# Schematic.net
KiCad netlist of a schematic drawn in Altium Designer
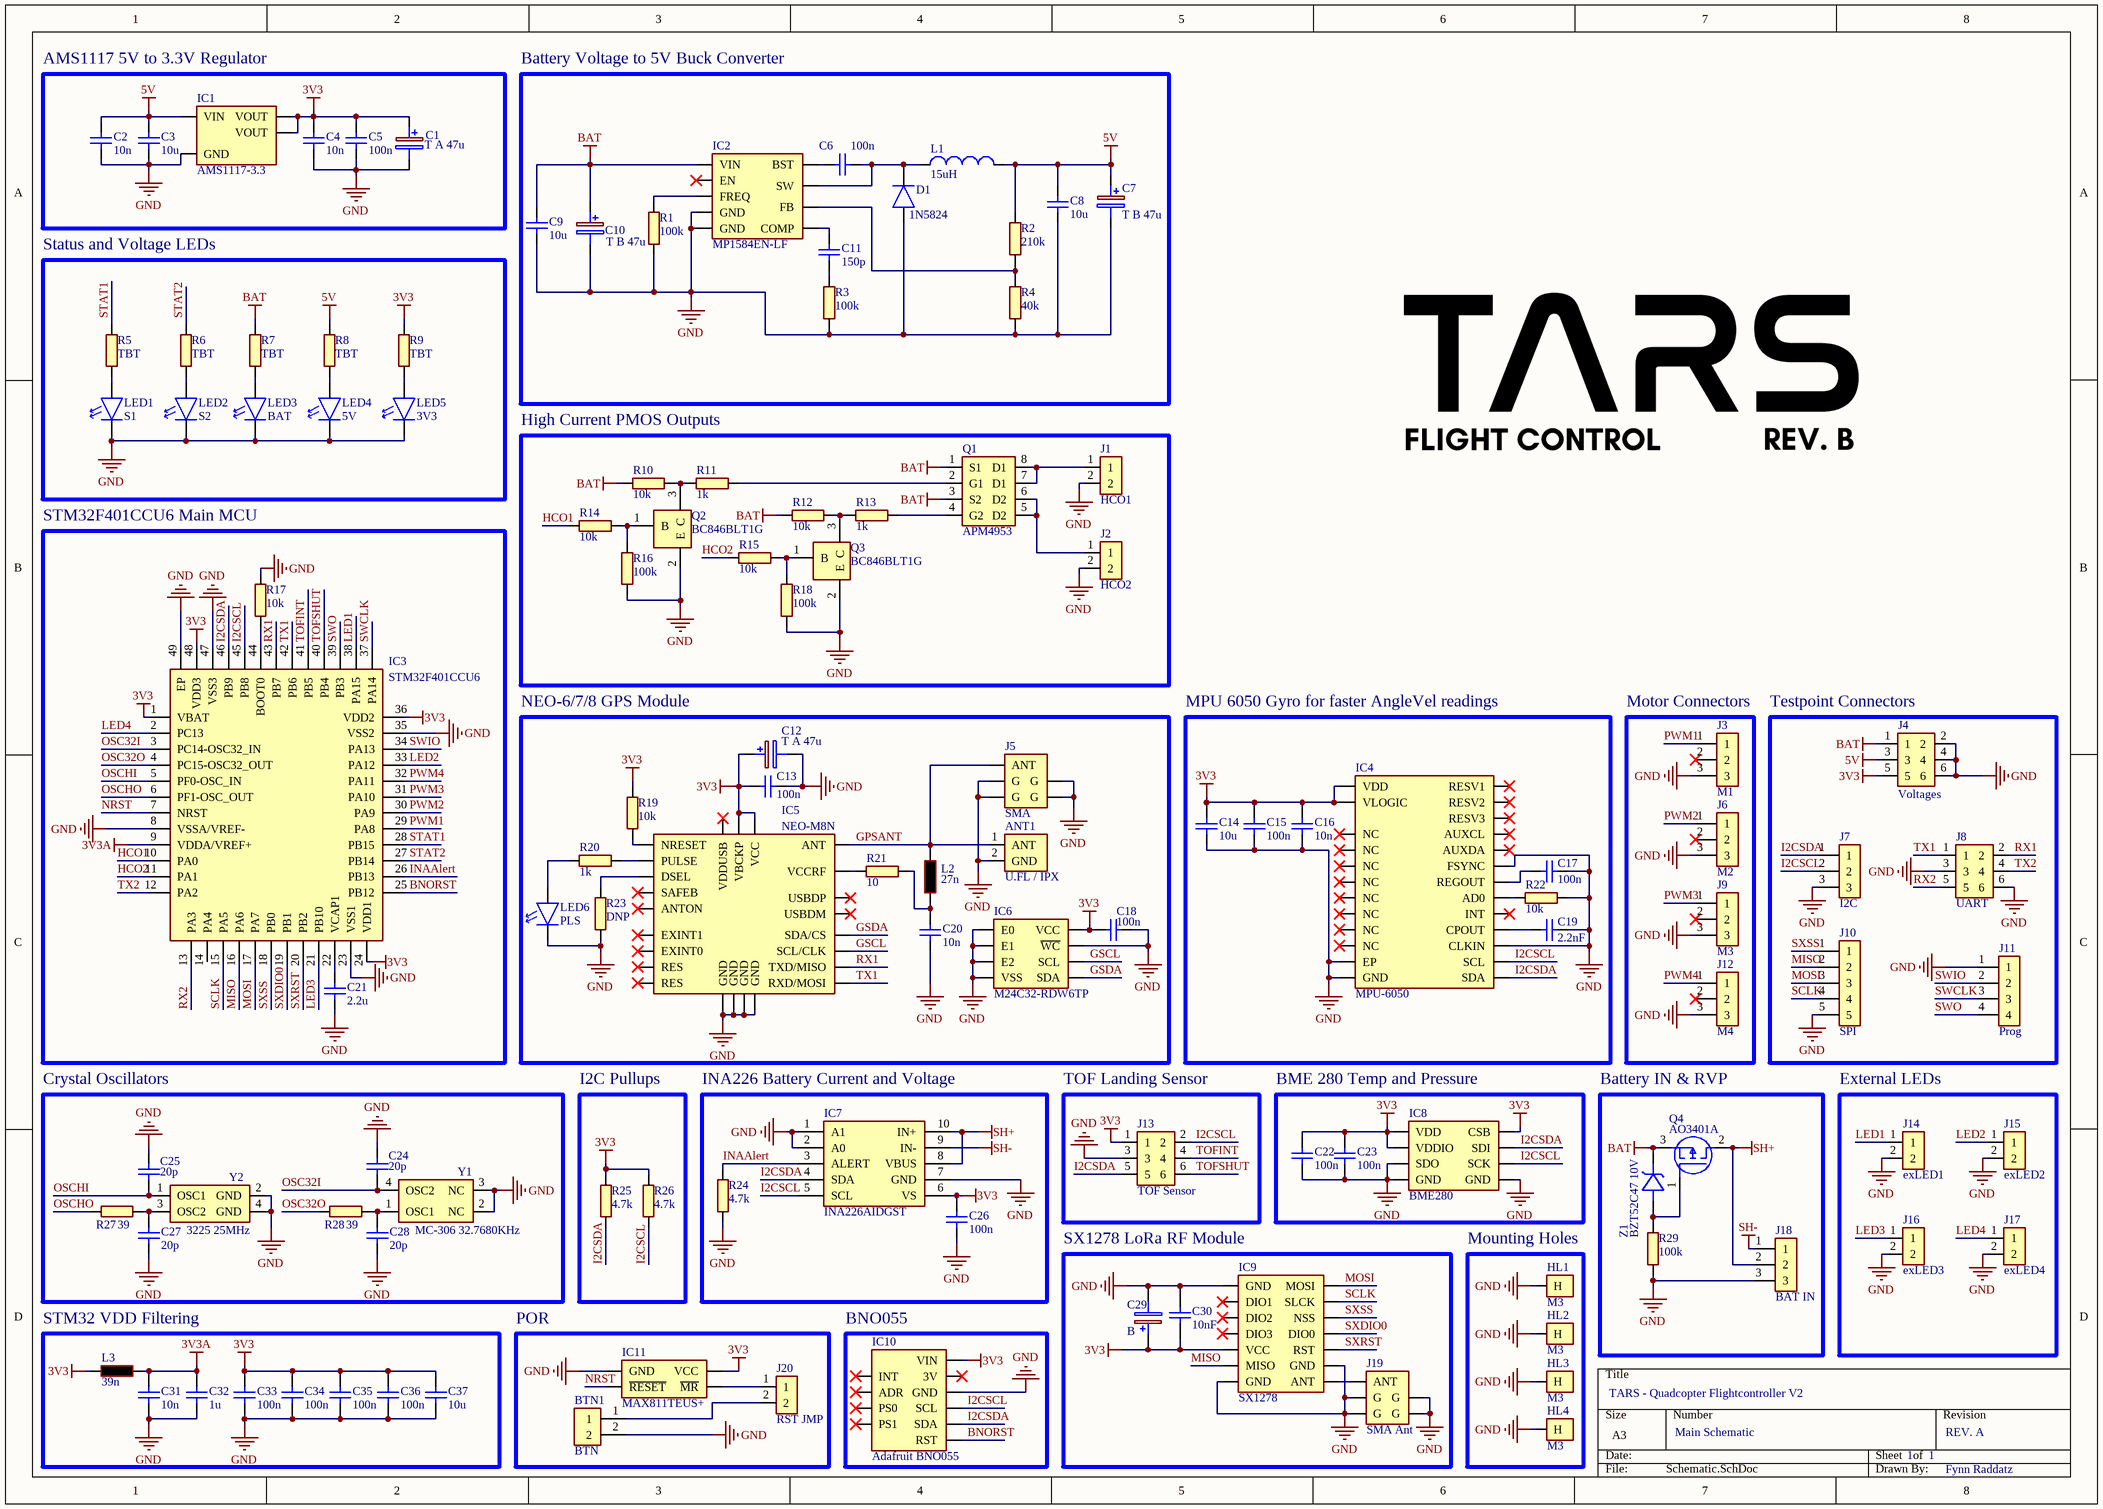
[diagram p0: Schematic.SchDoc]

(export (version "E")
  (design (tool "Eeschema 10.0.6"))
  (components
    (comp (ref "ANT1")
      (value "U.FL / IPX")
      (footprint "U.FL IPX Connector")
      (description "Connector")
      (libsource (lib "SamacSys") (part "U.FL SMD Antenna Connector"))
    )
    (comp (ref "BTN1")
      (value "BTN")
      (footprint "SamacSys:SMD-Button-3*6mm")
      (description "Button")
      (libsource (lib "SamacSys") (part "SMDButton-3*6mm"))
    )
    (comp (ref "C1")
      (value "T A 47u")
      (footprint "Tantal-A-1206")
      (description "Capacitor Tantalum")
      (libsource (lib "SamacSys") (part "TANTAL-A"))
    )
    (comp (ref "C2")
      (value "10n")
      (footprint "CAPC2012 METRIC")
      (description "Capacitor")
      (fields (field (name "MANUFACTURER_PART_NUMBER") "CL21B104KACNNNC"))
      (libsource (lib "SamacSys") (part "Cap 0805 IMP"))
    )
    (comp (ref "C3")
      (value "10u")
      (footprint "CAPC2012 METRIC")
      (description "Capacitor")
      (fields (field (name "MANUFACTURER_PART_NUMBER") "CL21B104KACNNNC"))
      (libsource (lib "SamacSys") (part "Cap 0805 IMP"))
    )
    (comp (ref "C4")
      (value "10n")
      (footprint "CAPC2012 METRIC")
      (description "Capacitor")
      (fields (field (name "MANUFACTURER_PART_NUMBER") "CL21B104KACNNNC"))
      (libsource (lib "SamacSys") (part "Cap 0805 IMP"))
    )
    (comp (ref "C5")
      (value "100n")
      (footprint "CAPC2012 METRIC")
      (description "Capacitor")
      (fields (field (name "MANUFACTURER_PART_NUMBER") "CL21B104KACNNNC"))
      (libsource (lib "SamacSys") (part "Cap 0805 IMP"))
    )
    (comp (ref "C6")
      (value "100n")
      (footprint "CAPC2012 METRIC")
      (description "Capacitor")
      (fields (field (name "MANUFACTURER_PART_NUMBER") "CL21B104KACNNNC"))
      (libsource (lib "SamacSys") (part "Cap 0805 IMP"))
    )
    (comp (ref "C7")
      (value "T B 47u")
      (footprint "Tantal-B-1210")
      (description "Capacitor Tantalum")
      (libsource (lib "SamacSys") (part "TANTAL-B"))
    )
    (comp (ref "C8")
      (value "10u")
      (footprint "CAPC2012 METRIC")
      (description "Capacitor")
      (fields (field (name "MANUFACTURER_PART_NUMBER") "CL21B104KACNNNC"))
      (libsource (lib "SamacSys") (part "Cap 0805 IMP"))
    )
    (comp (ref "C9")
      (value "10u")
      (footprint "CAPC2012 METRIC")
      (description "Capacitor")
      (fields (field (name "MANUFACTURER_PART_NUMBER") "CL21B104KACNNNC"))
      (libsource (lib "SamacSys") (part "Cap 0805 IMP"))
    )
    (comp (ref "C10")
      (value "T B 47u")
      (footprint "Tantal-B-1210")
      (description "Capacitor Tantalum")
      (libsource (lib "SamacSys") (part "TANTAL-B"))
    )
    (comp (ref "C11")
      (value "150p")
      (footprint "CAPC2012 METRIC")
      (description "Capacitor")
      (fields (field (name "MANUFACTURER_PART_NUMBER") "CL21B104KACNNNC"))
      (libsource (lib "SamacSys") (part "Cap 0805 IMP"))
    )
    (comp (ref "C12")
      (value "T A 47u")
      (footprint "Tantal-A-1206")
      (description "Capacitor Tantalum")
      (libsource (lib "") (part "TANTAL-A_1"))
    )
    (comp (ref "C13")
      (value "100n")
      (footprint "CAPC2012 METRIC")
      (description "Capacitor")
      (fields (field (name "MANUFACTURER_PART_NUMBER") "CL21B104KACNNNC"))
      (libsource (lib "SamacSys") (part "Cap 0805 IMP"))
    )
    (comp (ref "C14")
      (value "10u")
      (footprint "CAPC2012 METRIC")
      (description "Capacitor")
      (fields (field (name "MANUFACTURER_PART_NUMBER") "CL21B104KACNNNC"))
      (libsource (lib "SamacSys") (part "Cap 0805 IMP"))
    )
    (comp (ref "C15")
      (value "100n")
      (footprint "CAPC2012 METRIC")
      (description "Capacitor")
      (fields (field (name "MANUFACTURER_PART_NUMBER") "CL21B104KACNNNC"))
      (libsource (lib "SamacSys") (part "Cap 0805 IMP"))
    )
    (comp (ref "C16")
      (value "10n")
      (footprint "CAPC2012 METRIC")
      (description "Capacitor")
      (fields (field (name "MANUFACTURER_PART_NUMBER") "CL21B104KACNNNC"))
      (libsource (lib "SamacSys") (part "Cap 0805 IMP"))
    )
    (comp (ref "C17")
      (value "100n")
      (footprint "CAPC2012 METRIC")
      (description "Capacitor")
      (fields (field (name "MANUFACTURER_PART_NUMBER") "CL21B104KACNNNC"))
      (libsource (lib "SamacSys") (part "Cap 0805 IMP"))
    )
    (comp (ref "C18")
      (value "100n")
      (footprint "CAPC2012 METRIC")
      (description "Capacitor")
      (fields (field (name "MANUFACTURER_PART_NUMBER") "CL21B104KACNNNC"))
      (libsource (lib "SamacSys") (part "Cap 0805 IMP"))
    )
    (comp (ref "C19")
      (value "2.2nF")
      (footprint "CAPC2012 METRIC")
      (description "Capacitor")
      (fields (field (name "MANUFACTURER_PART_NUMBER") "CL21B104KACNNNC"))
      (libsource (lib "SamacSys") (part "Cap 0805 IMP"))
    )
    (comp (ref "C20")
      (value "10n")
      (footprint "CAPC2012 METRIC")
      (description "Capacitor")
      (fields (field (name "MANUFACTURER_PART_NUMBER") "CL21B104KACNNNC"))
      (libsource (lib "SamacSys") (part "Cap 0805 IMP"))
    )
    (comp (ref "C21")
      (value "2.2u")
      (footprint "CAPC2012 METRIC")
      (description "Capacitor")
      (fields (field (name "MANUFACTURER_PART_NUMBER") "CL21B104KACNNNC"))
      (libsource (lib "SamacSys") (part "Cap 0805 IMP"))
    )
    (comp (ref "C22")
      (value "100n")
      (footprint "CAPC2012 METRIC")
      (description "Capacitor")
      (fields (field (name "MANUFACTURER_PART_NUMBER") "CL21B104KACNNNC"))
      (libsource (lib "SamacSys") (part "Cap 0805 IMP"))
    )
    (comp (ref "C23")
      (value "100n")
      (footprint "CAPC2012 METRIC")
      (description "Capacitor")
      (fields (field (name "MANUFACTURER_PART_NUMBER") "CL21B104KACNNNC"))
      (libsource (lib "SamacSys") (part "Cap 0805 IMP"))
    )
    (comp (ref "C24")
      (value "20p")
      (footprint "CAPC2012 METRIC")
      (description "Capacitor")
      (fields (field (name "MANUFACTURER_PART_NUMBER") "CL21B104KACNNNC"))
      (libsource (lib "SamacSys") (part "Cap 0805 IMP"))
    )
    (comp (ref "C25")
      (value "20p")
      (footprint "CAPC2012 METRIC")
      (description "Capacitor")
      (fields (field (name "MANUFACTURER_PART_NUMBER") "CL21B104KACNNNC"))
      (libsource (lib "SamacSys") (part "Cap 0805 IMP"))
    )
    (comp (ref "C26")
      (value "100n")
      (footprint "CAPC2012 METRIC")
      (description "Capacitor")
      (fields (field (name "MANUFACTURER_PART_NUMBER") "CL21B104KACNNNC"))
      (libsource (lib "SamacSys") (part "Cap 0805 IMP"))
    )
    (comp (ref "C27")
      (value "20p")
      (footprint "CAPC2012 METRIC")
      (description "Capacitor")
      (fields (field (name "MANUFACTURER_PART_NUMBER") "CL21B104KACNNNC"))
      (libsource (lib "SamacSys") (part "Cap 0805 IMP"))
    )
    (comp (ref "C28")
      (value "20p")
      (footprint "CAPC2012 METRIC")
      (description "Capacitor")
      (fields (field (name "MANUFACTURER_PART_NUMBER") "CL21B104KACNNNC"))
      (libsource (lib "SamacSys") (part "Cap 0805 IMP"))
    )
    (comp (ref "C29")
      (value "B")
      (footprint "Tantal-B-1210")
      (description "Capacitor Tantalum")
      (libsource (lib "") (part "TANTAL-B_1"))
    )
    (comp (ref "C30")
      (value "10nF")
      (footprint "SamacSys:CAPC2012 METRIC")
      (description "Capacitor")
      (fields (field (name "MANUFACTURER_PART_NUMBER") "CL21B104KACNNNC"))
      (libsource (lib "SamacSys") (part "CL21B104KACNNNC"))
    )
    (comp (ref "C31")
      (value "10n")
      (footprint "CAPC2012 METRIC")
      (description "Capacitor")
      (fields (field (name "MANUFACTURER_PART_NUMBER") "CL21B104KACNNNC"))
      (libsource (lib "SamacSys") (part "Cap 0805 IMP"))
    )
    (comp (ref "C32")
      (value "1u")
      (footprint "CAPC2012 METRIC")
      (description "Capacitor")
      (fields (field (name "MANUFACTURER_PART_NUMBER") "CL21B104KACNNNC"))
      (libsource (lib "SamacSys") (part "Cap 0805 IMP"))
    )
    (comp (ref "C33")
      (value "100n")
      (footprint "CAPC2012 METRIC")
      (description "Capacitor")
      (fields (field (name "MANUFACTURER_PART_NUMBER") "CL21B104KACNNNC"))
      (libsource (lib "SamacSys") (part "Cap 0805 IMP"))
    )
    (comp (ref "C34")
      (value "100n")
      (footprint "CAPC2012 METRIC")
      (description "Capacitor")
      (fields (field (name "MANUFACTURER_PART_NUMBER") "CL21B104KACNNNC"))
      (libsource (lib "SamacSys") (part "Cap 0805 IMP"))
    )
    (comp (ref "C35")
      (value "100n")
      (footprint "CAPC2012 METRIC")
      (description "Capacitor")
      (fields (field (name "MANUFACTURER_PART_NUMBER") "CL21B104KACNNNC"))
      (libsource (lib "SamacSys") (part "Cap 0805 IMP"))
    )
    (comp (ref "C36")
      (value "100n")
      (footprint "CAPC2012 METRIC")
      (description "Capacitor")
      (fields (field (name "MANUFACTURER_PART_NUMBER") "CL21B104KACNNNC"))
      (libsource (lib "SamacSys") (part "Cap 0805 IMP"))
    )
    (comp (ref "C37")
      (value "10u")
      (footprint "CAPC2012 METRIC")
      (description "Capacitor")
      (fields (field (name "MANUFACTURER_PART_NUMBER") "CL21B104KACNNNC"))
      (libsource (lib "SamacSys") (part "Cap 0805 IMP"))
    )
    (comp (ref "D1")
      (value "1N5824")
      (footprint "SamacSys:DIOM5226X240N")
      (description "Diode")
      (fields
        (field (name "MANUFACTURER_PART_NUMBER") "B160-13-F")
        (field (name "MOUSER PART NUMBER") "621-B160-F")
      )
      (libsource (lib "SamacSys") (part "B160-13-F"))
    )
    (comp (ref "HL1")
      (value "M3")
      (footprint "DRILL HOLE M3")
      (description "Mounting Hole")
      (libsource (lib "SamacSys") (part "M3 Mouting Hole"))
    )
    (comp (ref "HL2")
      (value "M3")
      (footprint "DRILL HOLE M3")
      (description "Mounting Hole")
      (libsource (lib "SamacSys") (part "M3 Mouting Hole"))
    )
    (comp (ref "HL3")
      (value "M3")
      (footprint "DRILL HOLE M3")
      (description "Mounting Hole")
      (libsource (lib "SamacSys") (part "M3 Mouting Hole"))
    )
    (comp (ref "HL4")
      (value "M3")
      (footprint "DRILL HOLE M3")
      (description "Mounting Hole")
      (libsource (lib "SamacSys") (part "M3 Mouting Hole"))
    )
    (comp (ref "IC1")
      (value "AMS1117-3.3")
      (footprint "SamacSys:SOT229P700X180-4N")
      (description "Integrated Circuit")
      (libsource (lib "SamacSys") (part "AMS1117-3.3"))
    )
    (comp (ref "IC2")
      (value "MP1584EN-LF")
      (footprint "SamacSys:SOIC127P600X170-9N")
      (description "Integrated Circuit")
      (fields (field (name "MOUSER PART NUMBER") "946-MP1584ENLF"))
      (libsource (lib "SamacSys") (part "MP1584EN-LF"))
    )
    (comp (ref "IC3")
      (value "STM32F401CCU6")
      (footprint "SamacSys:QFN50P700X700X60-49N-D")
      (description "Integrated Circuit")
      (fields (field (name "MOUSER PART NUMBER") "511-STM32F401CCU6"))
      (libsource (lib "SamacSys") (part "STM32F401CCU6"))
    )
    (comp (ref "IC4")
      (value "MPU-6050")
      (footprint "SamacSys:MPU6050")
      (description "Integrated Circuit")
      (fields (field (name "MOUSER PART NUMBER") "410-MPU-6050"))
      (libsource (lib "SamacSys") (part "MPU-6050"))
    )
    (comp (ref "IC5")
      (value "NEO-M8N")
      (footprint "SamacSys:NEO-M8T")
      (description "Integrated Circuit")
      (fields (field (name "MANUFACTURER_PART_NUMBER") "NEO-M8N-0-10"))
      (libsource (lib "SamacSys") (part "NEO-M8N"))
    )
    (comp (ref "IC6")
      (value "M24C32-RDW6TP")
      (footprint "SamacSys:SOP65P640X120-8N")
      (description "Integrated Circuit")
      (fields (field (name "MOUSER PART NUMBER") "511-M24C32-RDW6TP"))
      (libsource (lib "SamacSys") (part "M24C32-RDW6TP"))
    )
    (comp (ref "IC7")
      (value "INA226AIDGST")
      (footprint "SamacSys:SOP50P490X110-10N")
      (description "Integrated Circuit")
      (fields (field (name "MOUSER PART NUMBER") "595-INA226AIDGST"))
      (libsource (lib "SamacSys") (part "INA226AIDGST"))
    )
    (comp (ref "IC8")
      (value "BME280")
      (footprint "SamacSys:MODBME280")
      (description "Integrated Circuit")
      (fields
        (field (name "MANUFACTURER_PART_NUMBER") "MOD-BME280")
        (field (name "MOUSER PART NUMBER") "909-MOD-BME280")
      )
      (libsource (lib "SamacSys") (part "MOD-BME280"))
    )
    (comp (ref "IC9")
      (value "SX1278")
      (footprint "SamacSys:SX1278")
      (description "RF")
      (libsource (lib "SamacSys") (part "SX1278"))
    )
    (comp (ref "IC10")
      (value "Adafruit BNO055")
      (footprint "Adfruit BNO055")
      (libsource (lib "SamacSys") (part "Adafruit BNO055"))
    )
    (comp (ref "IC11")
      (value "MAX811TEUS+")
      (footprint "SamacSys:MAX811REUST")
      (description "Integrated Circuit")
      (libsource (lib "SamacSys") (part "MAX811TEUS+"))
    )
    (comp (ref "J1")
      (value "HCO1")
      (footprint "SamacSys:HDRV2W110P0X254_1X2_508X254X854P")
      (description "Connector")
      (fields
        (field (name "MANUFACTURER_PART_NUMBER") "61300211121")
        (field (name "MOUSER PART NUMBER") "710-61300211121")
      )
      (libsource (lib "SamacSys") (part "61300211121"))
    )
    (comp (ref "J2")
      (value "HCO2")
      (footprint "SamacSys:HDRV2W110P0X254_1X2_508X254X854P")
      (description "Connector")
      (fields
        (field (name "MANUFACTURER_PART_NUMBER") "61300211121")
        (field (name "MOUSER PART NUMBER") "710-61300211121")
      )
      (libsource (lib "SamacSys") (part "61300211121"))
    )
    (comp (ref "J3")
      (value "M1")
      (footprint "SamacSys:HDRV3W64P0X254_1X3_762X254X869P")
      (description "Connector")
      (fields
        (field (name "MANUFACTURER_PART_NUMBER") "61300311121")
        (field (name "MOUSER PART NUMBER") "710-61300311121")
      )
      (libsource (lib "SamacSys") (part "61300311121"))
    )
    (comp (ref "J4")
      (value "Voltages")
      (footprint "SamacSys:HDRV6W64P0X254_1X6_1524X254X869P")
      (description "Connector")
      (fields
        (field (name "MANUFACTURER_PART_NUMBER") "61300611121")
        (field (name "MOUSER PART NUMBER") "710-61300611121")
      )
      (libsource (lib "SamacSys") (part "61300611121"))
    )
    (comp (ref "J5")
      (value "SMA")
      (footprint "SamacSys:PCBRPSMAFRAHT")
      (description "Connector")
      (fields
        (field (name "MANUFACTURER_PART_NUMBER") "PCB.RPSMAFRA.HT")
        (field (name "MOUSER PART NUMBER") "960-PCB.RPSMAFRA.HT")
      )
      (libsource (lib "SamacSys") (part "SMA Antenna"))
    )
    (comp (ref "J6")
      (value "M2")
      (footprint "SamacSys:HDRV3W64P0X254_1X3_762X254X869P")
      (description "Connector")
      (fields
        (field (name "MANUFACTURER_PART_NUMBER") "61300311121")
        (field (name "MOUSER PART NUMBER") "710-61300311121")
      )
      (libsource (lib "SamacSys") (part "61300311121"))
    )
    (comp (ref "J7")
      (value "I2C")
      (footprint "SamacSys:HDRV3W64P0X254_1X3_762X254X869P")
      (description "Connector")
      (fields
        (field (name "MANUFACTURER_PART_NUMBER") "61300311121")
        (field (name "MOUSER PART NUMBER") "710-61300311121")
      )
      (libsource (lib "SamacSys") (part "61300311121"))
    )
    (comp (ref "J8")
      (value "UART")
      (footprint "SamacSys:HDRV6W64P0X254_1X6_1524X254X869P")
      (description "Connector")
      (fields
        (field (name "MANUFACTURER_PART_NUMBER") "61300611121")
        (field (name "MOUSER PART NUMBER") "710-61300611121")
      )
      (libsource (lib "SamacSys") (part "61300611121"))
    )
    (comp (ref "J9")
      (value "M3")
      (footprint "SamacSys:HDRV3W64P0X254_1X3_762X254X869P")
      (description "Connector")
      (fields
        (field (name "MANUFACTURER_PART_NUMBER") "61300311121")
        (field (name "MOUSER PART NUMBER") "710-61300311121")
      )
      (libsource (lib "SamacSys") (part "61300311121"))
    )
    (comp (ref "J10")
      (value "SPI")
      (footprint "SamacSys:HDRV5W64P0X254_1X5_1270X254X854P")
      (description "Connector")
      (fields
        (field (name "MANUFACTURER_PART_NUMBER") "61300511121")
        (field (name "MOUSER PART NUMBER") "710-61300511121")
      )
      (libsource (lib "SamacSys") (part "61300511121"))
    )
    (comp (ref "J11")
      (value "Prog")
      (footprint "SamacSys:HDRV4W95P0X254_1X4_1016X254X854P")
      (description "Connector")
      (fields
        (field (name "MANUFACTURER_PART_NUMBER") "61300411121")
        (field (name "MOUSER PART NUMBER") "710-61300411121")
      )
      (libsource (lib "SamacSys") (part "61300411121"))
    )
    (comp (ref "J12")
      (value "M4")
      (footprint "SamacSys:HDRV3W64P0X254_1X3_762X254X869P")
      (description "Connector")
      (fields
        (field (name "MANUFACTURER_PART_NUMBER") "61300311121")
        (field (name "MOUSER PART NUMBER") "710-61300311121")
      )
      (libsource (lib "SamacSys") (part "61300311121"))
    )
    (comp (ref "J13")
      (value "TOF Sensor")
      (footprint "SamacSys:HDRV6W64P0X254_1X6_1524X254X869P")
      (description "Connector")
      (fields
        (field (name "MANUFACTURER_PART_NUMBER") "61300611121")
        (field (name "MOUSER PART NUMBER") "710-61300611121")
      )
      (libsource (lib "SamacSys") (part "61300611121"))
    )
    (comp (ref "J14")
      (value "exLED1")
      (footprint "SamacSys:HDRV2W110P0X254_1X2_508X254X854P")
      (description "Connector")
      (fields
        (field (name "MANUFACTURER_PART_NUMBER") "61300211121")
        (field (name "MOUSER PART NUMBER") "710-61300211121")
      )
      (libsource (lib "SamacSys") (part "61300211121"))
    )
    (comp (ref "J15")
      (value "exLED2")
      (footprint "SamacSys:HDRV2W110P0X254_1X2_508X254X854P")
      (description "Connector")
      (fields
        (field (name "MANUFACTURER_PART_NUMBER") "61300211121")
        (field (name "MOUSER PART NUMBER") "710-61300211121")
      )
      (libsource (lib "SamacSys") (part "61300211121"))
    )
    (comp (ref "J16")
      (value "exLED3")
      (footprint "SamacSys:HDRV2W110P0X254_1X2_508X254X854P")
      (description "Connector")
      (fields
        (field (name "MANUFACTURER_PART_NUMBER") "61300211121")
        (field (name "MOUSER PART NUMBER") "710-61300211121")
      )
      (libsource (lib "SamacSys") (part "61300211121"))
    )
    (comp (ref "J17")
      (value "exLED4")
      (footprint "SamacSys:HDRV2W110P0X254_1X2_508X254X854P")
      (description "Connector")
      (fields
        (field (name "MANUFACTURER_PART_NUMBER") "61300211121")
        (field (name "MOUSER PART NUMBER") "710-61300211121")
      )
      (libsource (lib "SamacSys") (part "61300211121"))
    )
    (comp (ref "J18")
      (value "BAT IN")
      (footprint "SamacSys:HDRV3W64P0X254_1X3_762X254X869P")
      (description "Connector")
      (fields
        (field (name "MANUFACTURER_PART_NUMBER") "61300311121")
        (field (name "MOUSER PART NUMBER") "710-61300311121")
      )
      (libsource (lib "SamacSys") (part "61300311121"))
    )
    (comp (ref "J19")
      (value "SMA Ant")
      (footprint "SamacSys:PCBRPSMAFRAHT")
      (description "Connector")
      (fields
        (field (name "MANUFACTURER_PART_NUMBER") "PCB.RPSMAFRA.HT")
        (field (name "MOUSER PART NUMBER") "960-PCB.RPSMAFRA.HT")
      )
      (libsource (lib "SamacSys") (part "SMA Antenna"))
    )
    (comp (ref "J20")
      (value "RST JMP")
      (footprint "SamacSys:HDRV2W110P0X254_1X2_508X254X854P")
      (description "Connector")
      (fields
        (field (name "MANUFACTURER_PART_NUMBER") "61300211121")
        (field (name "MOUSER PART NUMBER") "710-61300211121")
      )
      (libsource (lib "SamacSys") (part "61300211121"))
    )
    (comp (ref "L1")
      (value "15uH")
      (footprint "0630 Inductor")
      (description "Inductor")
      (libsource (lib "SamacSys") (part "0630 Inductor"))
    )
    (comp (ref "L2")
      (value "27n")
      (footprint "RESC2012X65N")
      (description "Inductor")
      (libsource (lib "SamacSys") (part "0805 Inductor"))
    )
    (comp (ref "L3")
      (value "39n")
      (footprint "RESC2012X65N")
      (description "Inductor")
      (libsource (lib "") (part "0805 Inductor_1"))
    )
    (comp (ref "LED1")
      (value "S1")
      (footprint "0805 LED")
      (description "LED")
      (libsource (lib "SamacSys") (part "LED 0805"))
    )
    (comp (ref "LED2")
      (value "S2")
      (footprint "0805 LED")
      (description "LED")
      (libsource (lib "SamacSys") (part "LED 0805"))
    )
    (comp (ref "LED3")
      (value "BAT")
      (footprint "0805 LED")
      (description "LED")
      (libsource (lib "SamacSys") (part "LED 0805"))
    )
    (comp (ref "LED4")
      (value "5V")
      (footprint "0805 LED")
      (description "LED")
      (libsource (lib "SamacSys") (part "LED 0805"))
    )
    (comp (ref "LED5")
      (value "3V3")
      (footprint "0805 LED")
      (description "LED")
      (libsource (lib "SamacSys") (part "LED 0805"))
    )
    (comp (ref "LED6")
      (value "PLS")
      (footprint "0805 LED")
      (description "LED")
      (libsource (lib "SamacSys") (part "LED 0805"))
    )
    (comp (ref "Q1")
      (value "APM4953")
      (footprint "SamacSys:SOIC127P600X175-8N")
      (description "MOSFET (P-Channel)")
      (libsource (lib "SamacSys") (part "APM4953"))
    )
    (comp (ref "Q2")
      (value "BC846BLT1G")
      (footprint "SamacSys:SOT96P237X111-3N")
      (description "Integrated Circuit")
      (fields (field (name "MOUSER PART NUMBER") "863-BC846BLT1G"))
      (libsource (lib "SamacSys") (part "BC846BLT1G"))
    )
    (comp (ref "Q3")
      (value "BC846BLT1G")
      (footprint "SamacSys:SOT96P237X111-3N")
      (description "Integrated Circuit")
      (fields (field (name "MOUSER PART NUMBER") "863-BC846BLT1G"))
      (libsource (lib "SamacSys") (part "BC846BLT1G"))
    )
    (comp (ref "Q4")
      (value "AO3401A")
      (footprint "SamacSys:SOT95P280X125-3N")
      (description "MOSFET (P-Channel)")
      (libsource (lib "SamacSys") (part "AO3401A"))
    )
    (comp (ref "R1")
      (value "100k")
      (footprint "SamacSys:RESC2012X65N")
      (description "Resistor")
      (fields (field (name "MANUFACTURER_PART_NUMBER") "RMCF0805ZT0R00"))
      (libsource (lib "SamacSys") (part "Res 0805"))
    )
    (comp (ref "R2")
      (value "210k")
      (footprint "SamacSys:RESC2012X65N")
      (description "Resistor")
      (fields (field (name "MANUFACTURER_PART_NUMBER") "RMCF0805ZT0R00"))
      (libsource (lib "SamacSys") (part "Res 0805"))
    )
    (comp (ref "R3")
      (value "100k")
      (footprint "SamacSys:RESC2012X65N")
      (description "Resistor")
      (fields (field (name "MANUFACTURER_PART_NUMBER") "RMCF0805ZT0R00"))
      (libsource (lib "SamacSys") (part "Res 0805"))
    )
    (comp (ref "R4")
      (value "40k")
      (footprint "SamacSys:RESC2012X65N")
      (description "Resistor")
      (fields (field (name "MANUFACTURER_PART_NUMBER") "RMCF0805ZT0R00"))
      (libsource (lib "SamacSys") (part "Res 0805"))
    )
    (comp (ref "R5")
      (value "TBT")
      (footprint "SamacSys:RESC2012X65N")
      (description "Resistor")
      (fields (field (name "MANUFACTURER_PART_NUMBER") "RMCF0805ZT0R00"))
      (libsource (lib "SamacSys") (part "Res 0805"))
    )
    (comp (ref "R6")
      (value "TBT")
      (footprint "SamacSys:RESC2012X65N")
      (description "Resistor")
      (fields (field (name "MANUFACTURER_PART_NUMBER") "RMCF0805ZT0R00"))
      (libsource (lib "SamacSys") (part "Res 0805"))
    )
    (comp (ref "R7")
      (value "TBT")
      (footprint "SamacSys:RESC2012X65N")
      (description "Resistor")
      (fields (field (name "MANUFACTURER_PART_NUMBER") "RMCF0805ZT0R00"))
      (libsource (lib "SamacSys") (part "Res 0805"))
    )
    (comp (ref "R8")
      (value "TBT")
      (footprint "SamacSys:RESC2012X65N")
      (description "Resistor")
      (fields (field (name "MANUFACTURER_PART_NUMBER") "RMCF0805ZT0R00"))
      (libsource (lib "SamacSys") (part "Res 0805"))
    )
    (comp (ref "R9")
      (value "TBT")
      (footprint "SamacSys:RESC2012X65N")
      (description "Resistor")
      (fields (field (name "MANUFACTURER_PART_NUMBER") "RMCF0805ZT0R00"))
      (libsource (lib "SamacSys") (part "Res 0805"))
    )
    (comp (ref "R10")
      (value "10k")
      (footprint "SamacSys:RESC2012X65N")
      (description "Resistor")
      (fields (field (name "MANUFACTURER_PART_NUMBER") "RMCF0805ZT0R00"))
      (libsource (lib "") (part "Res 0805_1"))
    )
    (comp (ref "R11")
      (value "1k")
      (footprint "SamacSys:RESC2012X65N")
      (description "Resistor")
      (fields (field (name "MANUFACTURER_PART_NUMBER") "RMCF0805ZT0R00"))
      (libsource (lib "") (part "Res 0805_1"))
    )
    (comp (ref "R12")
      (value "10k")
      (footprint "SamacSys:RESC2012X65N")
      (description "Resistor")
      (fields (field (name "MANUFACTURER_PART_NUMBER") "RMCF0805ZT0R00"))
      (libsource (lib "") (part "Res 0805_1"))
    )
    (comp (ref "R13")
      (value "1k")
      (footprint "SamacSys:RESC2012X65N")
      (description "Resistor")
      (fields (field (name "MANUFACTURER_PART_NUMBER") "RMCF0805ZT0R00"))
      (libsource (lib "") (part "Res 0805_1"))
    )
    (comp (ref "R14")
      (value "10k")
      (footprint "SamacSys:RESC2012X65N")
      (description "Resistor")
      (fields (field (name "MANUFACTURER_PART_NUMBER") "RMCF0805ZT0R00"))
      (libsource (lib "") (part "Res 0805_1"))
    )
    (comp (ref "R15")
      (value "10k")
      (footprint "SamacSys:RESC2012X65N")
      (description "Resistor")
      (fields (field (name "MANUFACTURER_PART_NUMBER") "RMCF0805ZT0R00"))
      (libsource (lib "") (part "Res 0805_1"))
    )
    (comp (ref "R16")
      (value "100k")
      (footprint "SamacSys:RESC2012X65N")
      (description "Resistor")
      (fields (field (name "MANUFACTURER_PART_NUMBER") "RMCF0805ZT0R00"))
      (libsource (lib "SamacSys") (part "Res 0805"))
    )
    (comp (ref "R17")
      (value "10k")
      (footprint "SamacSys:RESC2012X65N")
      (description "Resistor")
      (fields (field (name "MANUFACTURER_PART_NUMBER") "RMCF0805ZT0R00"))
      (libsource (lib "") (part "Res 0805_3"))
    )
    (comp (ref "R18")
      (value "100k")
      (footprint "SamacSys:RESC2012X65N")
      (description "Resistor")
      (fields (field (name "MANUFACTURER_PART_NUMBER") "RMCF0805ZT0R00"))
      (libsource (lib "SamacSys") (part "Res 0805"))
    )
    (comp (ref "R19")
      (value "10k")
      (footprint "SamacSys:RESC2012X65N")
      (description "Resistor")
      (fields (field (name "MANUFACTURER_PART_NUMBER") "RMCF0805ZT0R00"))
      (libsource (lib "") (part "Res 0805_3"))
    )
    (comp (ref "R20")
      (value "1k")
      (footprint "SamacSys:RESC2012X65N")
      (description "Resistor")
      (fields (field (name "MANUFACTURER_PART_NUMBER") "RMCF0805ZT0R00"))
      (libsource (lib "") (part "Res 0805_2"))
    )
    (comp (ref "R21")
      (value "10")
      (footprint "SamacSys:RESC2012X65N")
      (description "Resistor")
      (fields (field (name "MANUFACTURER_PART_NUMBER") "RMCF0805ZT0R00"))
      (libsource (lib "") (part "Res 0805_2"))
    )
    (comp (ref "R22")
      (value "10k")
      (footprint "SamacSys:RESC2012X65N")
      (description "Resistor")
      (fields (field (name "MANUFACTURER_PART_NUMBER") "RMCF0805ZT0R00"))
      (libsource (lib "") (part "Res 0805_2"))
    )
    (comp (ref "R23")
      (value "DNP")
      (footprint "SamacSys:RESC2012X65N")
      (description "Resistor")
      (fields (field (name "MANUFACTURER_PART_NUMBER") "RMCF0805ZT0R00"))
      (libsource (lib "SamacSys") (part "Res 0805"))
    )
    (comp (ref "R24")
      (value "4.7k")
      (footprint "SamacSys:RESC2012X65N")
      (description "Resistor")
      (fields (field (name "MANUFACTURER_PART_NUMBER") "RMCF0805ZT0R00"))
      (libsource (lib "") (part "Res 0805_3"))
    )
    (comp (ref "R25")
      (value "4.7k")
      (footprint "SamacSys:RESC2012X65N")
      (description "Resistor")
      (fields (field (name "MANUFACTURER_PART_NUMBER") "RMCF0805ZT0R00"))
      (libsource (lib "") (part "Res 0805_3"))
    )
    (comp (ref "R26")
      (value "4.7k")
      (footprint "SamacSys:RESC2012X65N")
      (description "Resistor")
      (fields (field (name "MANUFACTURER_PART_NUMBER") "RMCF0805ZT0R00"))
      (libsource (lib "") (part "Res 0805_3"))
    )
    (comp (ref "R27")
      (value "39")
      (footprint "SamacSys:RESC2012X65N")
      (description "Resistor")
      (fields (field (name "MANUFACTURER_PART_NUMBER") "RMCF0805ZT0R00"))
      (libsource (lib "") (part "Res 0805_2"))
    )
    (comp (ref "R28")
      (value "39")
      (footprint "SamacSys:RESC2012X65N")
      (description "Resistor")
      (fields (field (name "MANUFACTURER_PART_NUMBER") "RMCF0805ZT0R00"))
      (libsource (lib "") (part "Res 0805_2"))
    )
    (comp (ref "R29")
      (value "100k")
      (footprint "SamacSys:RESC2012X65N")
      (description "Resistor")
      (fields (field (name "MANUFACTURER_PART_NUMBER") "RMCF0805ZT0R00"))
      (libsource (lib "SamacSys") (part "Res 0805"))
    )
    (comp (ref "Y1")
      (value "MC-306 32.7680KHz")
      (footprint "SamacSys:MC306327680KA3ROHS")
      (description "Crystal or Oscillator")
      (fields
        (field (name "MANUFACTURER_PART_NUMBER") "MC-306 32.7680K-A3:ROHS")
        (field (name "MOUSER PART NUMBER") "732-MC306-32.7KA3R")
      )
      (libsource (lib "SamacSys") (part "MC-306_32.7680K-A3_ROHS"))
    )
    (comp (ref "Y2")
      (value "3225 25MHz")
      (footprint "SamacSys:TSX3225240000MF20GAC0")
      (description "Crystal or Oscillator")
      (fields
        (field (name "MANUFACTURER_PART_NUMBER") "TSX-3225 16.0000MF10U-B0")
        (field (name "MOUSER PART NUMBER") "732-322516MF10U-B0")
      )
      (libsource (lib "SamacSys") (part "3225 Oscillator"))
    )
    (comp (ref "Z1")
      (value "BZT52C47 10V")
      (footprint "SamacSys:BZT52C47")
      (description "Diode Zener")
      (fields
        (field (name "MANUFACTURER_PART_NUMBER") "BZT52C47")
        (field (name "MOUSER PART NUMBER") "821-BZT52C47")
      )
      (libsource (lib "SamacSys") (part "BZT52C47"))
    )
  )
  (nets
    (net (code "1") (name "/BNORST") (class "Default")
      (node (ref "IC10") (pin "10") (pinfunction "RST_10") (pintype "power_in"))
      (node (ref "IC3") (pin "25") (pinfunction "PB12_25") (pintype "passive"))
    )
    (net (code "2") (name "/GPSANT") (class "Default")
      (node (ref "ANT1") (pin "1") (pinfunction "ANT_1") (pintype "passive"))
      (node (ref "IC5") (pin "11") (pinfunction "ANT_11") (pintype "passive"))
      (node (ref "J5") (pin "1") (pinfunction "ANT_1") (pintype "passive"))
      (node (ref "L2") (pin "2") (pinfunction "2_2") (pintype "passive"))
    )
    (net (code "3") (name "/GSCL") (class "Default")
      (node (ref "IC5") (pin "19") (pinfunction "SCL/CLK_19") (pintype "passive"))
      (node (ref "IC6") (pin "6") (pinfunction "SCL_6") (pintype "passive"))
    )
    (net (code "4") (name "/GSDA") (class "Default")
      (node (ref "IC5") (pin "18") (pinfunction "SDA/CS_18") (pintype "passive"))
      (node (ref "IC6") (pin "5") (pinfunction "SDA_5") (pintype "passive"))
    )
    (net (code "5") (name "/HCO1") (class "Default")
      (node (ref "IC3") (pin "10") (pinfunction "PA0_10") (pintype "passive"))
      (node (ref "R14") (pin "1") (pinfunction "1_1") (pintype "passive"))
    )
    (net (code "6") (name "/HCO2") (class "Default")
      (node (ref "IC3") (pin "11") (pinfunction "PA1_11") (pintype "passive"))
      (node (ref "R15") (pin "1") (pinfunction "1_1") (pintype "passive"))
    )
    (net (code "7") (name "/I2CSCL") (class "Default")
      (node (ref "IC10") (pin "8") (pinfunction "SCL_8") (pintype "power_in"))
      (node (ref "IC3") (pin "45") (pinfunction "PB8_45") (pintype "passive"))
      (node (ref "IC4") (pin "23") (pinfunction "SCL_23") (pintype "passive"))
      (node (ref "IC7") (pin "5") (pinfunction "SCL_5") (pintype "passive"))
      (node (ref "IC8") (pin "4") (pinfunction "SCK_4") (pintype "passive"))
      (node (ref "J13") (pin "2") (pinfunction "2_2") (pintype "passive"))
      (node (ref "J7") (pin "2") (pinfunction "2_2") (pintype "passive"))
      (node (ref "R26") (pin "1") (pinfunction "1_1") (pintype "passive"))
    )
    (net (code "8") (name "/I2CSDA") (class "Default")
      (node (ref "IC10") (pin "9") (pinfunction "SDA_9") (pintype "power_in"))
      (node (ref "IC3") (pin "46") (pinfunction "PB9_46") (pintype "passive"))
      (node (ref "IC4") (pin "24") (pinfunction "SDA_24") (pintype "passive"))
      (node (ref "IC7") (pin "4") (pinfunction "SDA_4") (pintype "passive"))
      (node (ref "IC8") (pin "3") (pinfunction "SDI_3") (pintype "passive"))
      (node (ref "J13") (pin "5") (pinfunction "5_5") (pintype "passive"))
      (node (ref "J7") (pin "1") (pinfunction "1_1") (pintype "passive"))
      (node (ref "R25") (pin "1") (pinfunction "1_1") (pintype "passive"))
    )
    (net (code "9") (name "/INAAlert") (class "Default")
      (node (ref "IC3") (pin "26") (pinfunction "PB13_26") (pintype "passive"))
      (node (ref "IC7") (pin "3") (pinfunction "ALERT_3") (pintype "passive"))
      (node (ref "R24") (pin "2") (pinfunction "2_2") (pintype "passive"))
    )
    (net (code "10") (name "/LED1") (class "Default")
      (node (ref "IC3") (pin "38") (pinfunction "PA15_38") (pintype "passive"))
      (node (ref "J14") (pin "1") (pinfunction "1_1") (pintype "passive"))
    )
    (net (code "11") (name "/LED2") (class "Default")
      (node (ref "IC3") (pin "33") (pinfunction "PA12_33") (pintype "passive"))
      (node (ref "J15") (pin "1") (pinfunction "1_1") (pintype "passive"))
    )
    (net (code "12") (name "/LED3") (class "Default")
      (node (ref "IC3") (pin "21") (pinfunction "PB10_21") (pintype "passive"))
      (node (ref "J16") (pin "1") (pinfunction "1_1") (pintype "passive"))
    )
    (net (code "13") (name "/LED4") (class "Default")
      (node (ref "IC3") (pin "2") (pinfunction "PC13_2") (pintype "passive"))
      (node (ref "J17") (pin "1") (pinfunction "1_1") (pintype "passive"))
    )
    (net (code "14") (name "/MISO") (class "Default")
      (node (ref "IC3") (pin "16") (pinfunction "PA6_16") (pintype "passive"))
      (node (ref "IC9") (pin "6") (pinfunction "MISO_6") (pintype "passive"))
      (node (ref "J10") (pin "2") (pinfunction "2_2") (pintype "passive"))
    )
    (net (code "15") (name "/MOSI") (class "Default")
      (node (ref "IC3") (pin "17") (pinfunction "PA7_17") (pintype "passive"))
      (node (ref "IC9") (pin "7") (pinfunction "MOSI_7") (pintype "passive"))
      (node (ref "J10") (pin "3") (pinfunction "3_3") (pintype "passive"))
    )
    (net (code "16") (name "/NRST") (class "Default")
      (node (ref "IC11") (pin "2") (pinfunction "~{RESET}_2") (pintype "passive"))
      (node (ref "IC3") (pin "7") (pinfunction "NRST_7") (pintype "passive"))
    )
    (net (code "17") (name "/OSC32I") (class "Default")
      (node (ref "C24") (pin "1") (pinfunction "1_1") (pintype "passive"))
      (node (ref "IC3") (pin "3") (pinfunction "PC14-OSC32_IN_3") (pintype "passive"))
      (node (ref "Y1") (pin "4") (pinfunction "OSC2_4") (pintype "passive"))
    )
    (net (code "18") (name "/OSC32O") (class "Default")
      (node (ref "IC3") (pin "4") (pinfunction "PC15-OSC32_OUT_4") (pintype "passive"))
      (node (ref "R28") (pin "2") (pinfunction "2_2") (pintype "passive"))
    )
    (net (code "19") (name "/OSCHI") (class "Default")
      (node (ref "C25") (pin "1") (pinfunction "1_1") (pintype "passive"))
      (node (ref "IC3") (pin "5") (pinfunction "PF0-OSC_IN_5") (pintype "passive"))
      (node (ref "Y2") (pin "1") (pinfunction "OSC1_1") (pintype "passive"))
    )
    (net (code "20") (name "/OSCHO") (class "Default")
      (node (ref "IC3") (pin "6") (pinfunction "PF1-OSC_OUT_6") (pintype "passive"))
      (node (ref "R27") (pin "2") (pinfunction "2_2") (pintype "passive"))
    )
    (net (code "21") (name "/PWM1") (class "Default")
      (node (ref "IC3") (pin "29") (pinfunction "PA8_29") (pintype "passive"))
      (node (ref "J3") (pin "1") (pinfunction "1_1") (pintype "passive"))
    )
    (net (code "22") (name "/PWM2") (class "Default")
      (node (ref "IC3") (pin "30") (pinfunction "PA9_30") (pintype "passive"))
      (node (ref "J6") (pin "1") (pinfunction "1_1") (pintype "passive"))
    )
    (net (code "23") (name "/PWM3") (class "Default")
      (node (ref "IC3") (pin "31") (pinfunction "PA10_31") (pintype "passive"))
      (node (ref "J9") (pin "1") (pinfunction "1_1") (pintype "passive"))
    )
    (net (code "24") (name "/PWM4") (class "Default")
      (node (ref "IC3") (pin "32") (pinfunction "PA11_32") (pintype "passive"))
      (node (ref "J12") (pin "1") (pinfunction "1_1") (pintype "passive"))
    )
    (net (code "25") (name "/RX1") (class "Default")
      (node (ref "IC3") (pin "43") (pinfunction "PB7_43") (pintype "passive"))
      (node (ref "IC5") (pin "20") (pinfunction "TXD/MISO_20") (pintype "passive"))
      (node (ref "J8") (pin "2") (pinfunction "2_2") (pintype "passive"))
    )
    (net (code "26") (name "/RX2") (class "Default")
      (node (ref "IC3") (pin "13") (pinfunction "PA3_13") (pintype "passive"))
      (node (ref "J8") (pin "5") (pinfunction "5_5") (pintype "passive"))
    )
    (net (code "27") (name "/SCLK") (class "Default")
      (node (ref "IC3") (pin "15") (pinfunction "PA5_15") (pintype "passive"))
      (node (ref "IC9") (pin "8") (pinfunction "SLCK_8") (pintype "passive"))
      (node (ref "J10") (pin "4") (pinfunction "4_4") (pintype "passive"))
    )
    (net (code "28") (name "/STAT1") (class "Default")
      (node (ref "IC3") (pin "28") (pinfunction "PB15_28") (pintype "passive"))
      (node (ref "R5") (pin "1") (pinfunction "1_1") (pintype "passive"))
    )
    (net (code "29") (name "/STAT2") (class "Default")
      (node (ref "IC3") (pin "27") (pinfunction "PB14_27") (pintype "passive"))
      (node (ref "R6") (pin "1") (pinfunction "1_1") (pintype "passive"))
    )
    (net (code "30") (name "/SWCLK") (class "Default")
      (node (ref "IC3") (pin "37") (pinfunction "PA14_37") (pintype "passive"))
      (node (ref "J11") (pin "3") (pinfunction "3_3") (pintype "passive"))
    )
    (net (code "31") (name "/SWIO") (class "Default")
      (node (ref "IC3") (pin "34") (pinfunction "PA13_34") (pintype "passive"))
      (node (ref "J11") (pin "2") (pinfunction "2_2") (pintype "passive"))
    )
    (net (code "32") (name "/SWO") (class "Default")
      (node (ref "IC3") (pin "39") (pinfunction "PB3_39") (pintype "passive"))
      (node (ref "J11") (pin "4") (pinfunction "4_4") (pintype "passive"))
    )
    (net (code "33") (name "/SXDIO0") (class "Default")
      (node (ref "IC3") (pin "19") (pinfunction "PB1_19") (pintype "passive"))
      (node (ref "IC9") (pin "10") (pinfunction "DIO0_10") (pintype "passive"))
    )
    (net (code "34") (name "/SXRST") (class "Default")
      (node (ref "IC3") (pin "20") (pinfunction "PB2_20") (pintype "passive"))
      (node (ref "IC9") (pin "11") (pinfunction "RST_11") (pintype "passive"))
    )
    (net (code "35") (name "/SXSS") (class "Default")
      (node (ref "IC3") (pin "18") (pinfunction "PB0_18") (pintype "passive"))
      (node (ref "IC9") (pin "9") (pinfunction "NSS_9") (pintype "passive"))
      (node (ref "J10") (pin "1") (pinfunction "1_1") (pintype "passive"))
    )
    (net (code "36") (name "/TOFINT") (class "Default")
      (node (ref "IC3") (pin "41") (pinfunction "PB5_41") (pintype "passive"))
      (node (ref "J13") (pin "4") (pinfunction "4_4") (pintype "passive"))
    )
    (net (code "37") (name "/TOFSHUT") (class "Default")
      (node (ref "IC3") (pin "40") (pinfunction "PB4_40") (pintype "passive"))
      (node (ref "J13") (pin "6") (pinfunction "6_6") (pintype "passive"))
    )
    (net (code "38") (name "/TX1") (class "Default")
      (node (ref "IC3") (pin "42") (pinfunction "PB6_42") (pintype "passive"))
      (node (ref "IC5") (pin "21") (pinfunction "RXD/MOSI_21") (pintype "passive"))
      (node (ref "J8") (pin "1") (pinfunction "1_1") (pintype "passive"))
    )
    (net (code "39") (name "/TX2") (class "Default")
      (node (ref "IC3") (pin "12") (pinfunction "PA2_12") (pintype "passive"))
      (node (ref "J8") (pin "4") (pinfunction "4_4") (pintype "passive"))
    )
    (net (code "40") (name "3V3") (class "Default")
      (node (ref "C1") (pin "1") (pinfunction "+_1") (pintype "passive"))
      (node (ref "C12") (pin "1") (pinfunction "+_1") (pintype "passive"))
      (node (ref "C13") (pin "2") (pinfunction "2_2") (pintype "passive"))
      (node (ref "C14") (pin "1") (pinfunction "1_1") (pintype "passive"))
      (node (ref "C15") (pin "1") (pinfunction "1_1") (pintype "passive"))
      (node (ref "C16") (pin "1") (pinfunction "1_1") (pintype "passive"))
      (node (ref "C18") (pin "2") (pinfunction "2_2") (pintype "passive"))
      (node (ref "C22") (pin "1") (pinfunction "1_1") (pintype "passive"))
      (node (ref "C23") (pin "1") (pinfunction "1_1") (pintype "passive"))
      (node (ref "C26") (pin "2") (pinfunction "2_2") (pintype "passive"))
      (node (ref "C29") (pin "1") (pinfunction "+_1") (pintype "passive"))
      (node (ref "C30") (pin "2") (pinfunction "2_2") (pintype "passive"))
      (node (ref "C33") (pin "2") (pinfunction "2_2") (pintype "passive"))
      (node (ref "C34") (pin "2") (pinfunction "2_2") (pintype "passive"))
      (node (ref "C35") (pin "2") (pinfunction "2_2") (pintype "passive"))
      (node (ref "C36") (pin "2") (pinfunction "2_2") (pintype "passive"))
      (node (ref "C37") (pin "2") (pinfunction "2_2") (pintype "passive"))
      (node (ref "C4") (pin "1") (pinfunction "1_1") (pintype "passive"))
      (node (ref "C5") (pin "1") (pinfunction "1_1") (pintype "passive"))
      (node (ref "IC1") (pin "2") (pinfunction "VOUT_2") (pintype "passive"))
      (node (ref "IC1") (pin "4") (pinfunction "VOUT_4") (pintype "passive"))
      (node (ref "IC10") (pin "5") (pinfunction "VIN_5") (pintype "power_in"))
      (node (ref "IC11") (pin "4") (pinfunction "VCC_4") (pintype "passive"))
      (node (ref "IC3") (pin "1") (pinfunction "VBAT_1") (pintype "passive"))
      (node (ref "IC3") (pin "24") (pinfunction "VDD1_24") (pintype "power_in"))
      (node (ref "IC3") (pin "36") (pinfunction "VDD2_36") (pintype "power_in"))
      (node (ref "IC3") (pin "48") (pinfunction "VDD3_48") (pintype "power_in"))
      (node (ref "IC4") (pin "13") (pinfunction "VDD_13") (pintype "passive"))
      (node (ref "IC4") (pin "8") (pinfunction "VLOGIC_8") (pintype "passive"))
      (node (ref "IC5") (pin "22") (pinfunction "VBCKP_22") (pintype "passive"))
      (node (ref "IC5") (pin "23") (pinfunction "VCC_23") (pintype "passive"))
      (node (ref "IC6") (pin "8") (pinfunction "VCC_8") (pintype "passive"))
      (node (ref "IC7") (pin "6") (pinfunction "VS_6") (pintype "passive"))
      (node (ref "IC8") (pin "2") (pinfunction "CSB_2") (pintype "passive"))
      (node (ref "IC8") (pin "6") (pinfunction "VDDIO_6") (pintype "passive"))
      (node (ref "IC8") (pin "8") (pinfunction "VDD_8") (pintype "passive"))
      (node (ref "IC9") (pin "5") (pinfunction "VCC_5") (pintype "passive"))
      (node (ref "J13") (pin "1") (pinfunction "1_1") (pintype "passive"))
      (node (ref "J4") (pin "5") (pinfunction "5_5") (pintype "passive"))
      (node (ref "L3") (pin "2") (pinfunction "2_2") (pintype "passive"))
      (node (ref "R19") (pin "2") (pinfunction "2_2") (pintype "passive"))
      (node (ref "R25") (pin "2") (pinfunction "2_2") (pintype "passive"))
      (node (ref "R26") (pin "2") (pinfunction "2_2") (pintype "passive"))
      (node (ref "R9") (pin "1") (pinfunction "1_1") (pintype "passive"))
    )
    (net (code "41") (name "3V3A") (class "Default")
      (node (ref "C31") (pin "2") (pinfunction "2_2") (pintype "passive"))
      (node (ref "C32") (pin "2") (pinfunction "2_2") (pintype "passive"))
      (node (ref "IC3") (pin "9") (pinfunction "VDDA/VREF+_9") (pintype "power_in"))
      (node (ref "L3") (pin "1") (pinfunction "1_1") (pintype "passive"))
    )
    (net (code "42") (name "5V") (class "Default")
      (node (ref "C2") (pin "1") (pinfunction "1_1") (pintype "passive"))
      (node (ref "C3") (pin "1") (pinfunction "1_1") (pintype "passive"))
      (node (ref "C7") (pin "1") (pinfunction "+_1") (pintype "passive"))
      (node (ref "C8") (pin "1") (pinfunction "1_1") (pintype "passive"))
      (node (ref "IC1") (pin "3") (pinfunction "VIN_3") (pintype "passive"))
      (node (ref "J4") (pin "3") (pinfunction "3_3") (pintype "passive"))
      (node (ref "L1") (pin "2") (pinfunction "2_2") (pintype "passive"))
      (node (ref "R2") (pin "1") (pinfunction "1_1") (pintype "passive"))
      (node (ref "R8") (pin "1") (pinfunction "1_1") (pintype "passive"))
    )
    (net (code "43") (name "BAT") (class "Default")
      (node (ref "C10") (pin "1") (pinfunction "+_1") (pintype "passive"))
      (node (ref "C9") (pin "1") (pinfunction "1_1") (pintype "passive"))
      (node (ref "IC2") (pin "7") (pinfunction "VIN_7") (pintype "passive"))
      (node (ref "J4") (pin "1") (pinfunction "1_1") (pintype "passive"))
      (node (ref "Q1") (pin "1") (pinfunction "S1_1") (pintype "passive"))
      (node (ref "Q1") (pin "3") (pinfunction "S2_3") (pintype "passive"))
      (node (ref "Q4") (pin "3") (pinfunction "S_3") (pintype "passive"))
      (node (ref "R10") (pin "1") (pinfunction "1_1") (pintype "passive"))
      (node (ref "R12") (pin "1") (pinfunction "1_1") (pintype "passive"))
      (node (ref "R7") (pin "1") (pinfunction "1_1") (pintype "passive"))
      (node (ref "Z1") (pin "1") (pinfunction "K_1") (pintype "passive"))
    )
    (net (code "44") (name "GND") (class "Default")
      (node (ref "ANT1") (pin "2") (pinfunction "GND_2") (pintype "passive"))
      (node (ref "BTN1") (pin "2") (pinfunction "2_2") (pintype "passive"))
      (node (ref "C1") (pin "2") (pinfunction "-_2") (pintype "passive"))
      (node (ref "C10") (pin "2") (pinfunction "-_2") (pintype "passive"))
      (node (ref "C12") (pin "2") (pinfunction "-_2") (pintype "passive"))
      (node (ref "C13") (pin "1") (pinfunction "1_1") (pintype "passive"))
      (node (ref "C14") (pin "2") (pinfunction "2_2") (pintype "passive"))
      (node (ref "C15") (pin "2") (pinfunction "2_2") (pintype "passive"))
      (node (ref "C16") (pin "2") (pinfunction "2_2") (pintype "passive"))
      (node (ref "C17") (pin "2") (pinfunction "2_2") (pintype "passive"))
      (node (ref "C18") (pin "1") (pinfunction "1_1") (pintype "passive"))
      (node (ref "C19") (pin "2") (pinfunction "2_2") (pintype "passive"))
      (node (ref "C2") (pin "2") (pinfunction "2_2") (pintype "passive"))
      (node (ref "C20") (pin "2") (pinfunction "2_2") (pintype "passive"))
      (node (ref "C21") (pin "1") (pinfunction "1_1") (pintype "passive"))
      (node (ref "C22") (pin "2") (pinfunction "2_2") (pintype "passive"))
      (node (ref "C23") (pin "2") (pinfunction "2_2") (pintype "passive"))
      (node (ref "C24") (pin "2") (pinfunction "2_2") (pintype "passive"))
      (node (ref "C25") (pin "2") (pinfunction "2_2") (pintype "passive"))
      (node (ref "C26") (pin "1") (pinfunction "1_1") (pintype "passive"))
      (node (ref "C27") (pin "1") (pinfunction "1_1") (pintype "passive"))
      (node (ref "C28") (pin "1") (pinfunction "1_1") (pintype "passive"))
      (node (ref "C29") (pin "2") (pinfunction "-_2") (pintype "passive"))
      (node (ref "C3") (pin "2") (pinfunction "2_2") (pintype "passive"))
      (node (ref "C30") (pin "1") (pinfunction "1_1") (pintype "passive"))
      (node (ref "C31") (pin "1") (pinfunction "1_1") (pintype "passive"))
      (node (ref "C32") (pin "1") (pinfunction "1_1") (pintype "passive"))
      (node (ref "C33") (pin "1") (pinfunction "1_1") (pintype "passive"))
      (node (ref "C34") (pin "1") (pinfunction "1_1") (pintype "passive"))
      (node (ref "C35") (pin "1") (pinfunction "1_1") (pintype "passive"))
      (node (ref "C36") (pin "1") (pinfunction "1_1") (pintype "passive"))
      (node (ref "C37") (pin "1") (pinfunction "1_1") (pintype "passive"))
      (node (ref "C4") (pin "2") (pinfunction "2_2") (pintype "passive"))
      (node (ref "C5") (pin "2") (pinfunction "2_2") (pintype "passive"))
      (node (ref "C7") (pin "2") (pinfunction "-_2") (pintype "passive"))
      (node (ref "C8") (pin "2") (pinfunction "2_2") (pintype "passive"))
      (node (ref "C9") (pin "2") (pinfunction "2_2") (pintype "passive"))
      (node (ref "D1") (pin "2") (pinfunction "A_2") (pintype "passive"))
      (node (ref "HL1") (pin "1") (pinfunction "H_1") (pintype "passive"))
      (node (ref "HL2") (pin "1") (pinfunction "H_1") (pintype "passive"))
      (node (ref "HL3") (pin "1") (pinfunction "H_1") (pintype "passive"))
      (node (ref "HL4") (pin "1") (pinfunction "H_1") (pintype "passive"))
      (node (ref "IC1") (pin "1") (pinfunction "GND_1") (pintype "passive"))
      (node (ref "IC10") (pin "7") (pinfunction "GND_7") (pintype "power_in"))
      (node (ref "IC11") (pin "1") (pinfunction "GND_1") (pintype "passive"))
      (node (ref "IC2") (pin "5") (pinfunction "GND_5") (pintype "passive"))
      (node (ref "IC2") (pin "9") (pinfunction "GND_9") (pintype "passive"))
      (node (ref "IC3") (pin "23") (pinfunction "VSS1_23") (pintype "power_in"))
      (node (ref "IC3") (pin "35") (pinfunction "VSS2_35") (pintype "power_in"))
      (node (ref "IC3") (pin "47") (pinfunction "VSS3_47") (pintype "power_in"))
      (node (ref "IC3") (pin "49") (pinfunction "EP_49") (pintype "passive"))
      (node (ref "IC3") (pin "8") (pinfunction "VSSA/VREF-_8") (pintype "power_in"))
      (node (ref "IC4") (pin "1") (pinfunction "CLKIN_1") (pintype "passive"))
      (node (ref "IC4") (pin "11") (pinfunction "FSYNC_11") (pintype "passive"))
      (node (ref "IC4") (pin "18") (pinfunction "GND_18") (pintype "passive"))
      (node (ref "IC4") (pin "25") (pinfunction "EP_25") (pintype "passive"))
      (node (ref "IC5") (pin "10") (pinfunction "GND_10") (pintype "passive"))
      (node (ref "IC5") (pin "12") (pinfunction "GND_12") (pintype "passive"))
      (node (ref "IC5") (pin "13") (pinfunction "GND_13") (pintype "passive"))
      (node (ref "IC5") (pin "24") (pinfunction "GND_24") (pintype "passive"))
      (node (ref "IC6") (pin "1") (pinfunction "E0_1") (pintype "passive"))
      (node (ref "IC6") (pin "2") (pinfunction "E1_2") (pintype "passive"))
      (node (ref "IC6") (pin "3") (pinfunction "E2_3") (pintype "passive"))
      (node (ref "IC6") (pin "4") (pinfunction "VSS_4") (pintype "passive"))
      (node (ref "IC6") (pin "7") (pinfunction "~{WC}_7") (pintype "passive"))
      (node (ref "IC7") (pin "1") (pinfunction "A1_1") (pintype "passive"))
      (node (ref "IC7") (pin "2") (pinfunction "A0_2") (pintype "passive"))
      (node (ref "IC7") (pin "7") (pinfunction "GND_7") (pintype "passive"))
      (node (ref "IC8") (pin "1") (pinfunction "GND_1") (pintype "passive"))
      (node (ref "IC8") (pin "5") (pinfunction "SDO_5") (pintype "passive"))
      (node (ref "IC8") (pin "7") (pinfunction "GND_7") (pintype "passive"))
      (node (ref "IC9") (pin "1") (pinfunction "GND_1") (pintype "passive"))
      (node (ref "IC9") (pin "12") (pinfunction "GND_12") (pintype "passive"))
      (node (ref "IC9") (pin "14") (pinfunction "GND_14") (pintype "passive"))
      (node (ref "J1") (pin "2") (pinfunction "2_2") (pintype "passive"))
      (node (ref "J10") (pin "5") (pinfunction "5_5") (pintype "passive"))
      (node (ref "J11") (pin "1") (pinfunction "1_1") (pintype "passive"))
      (node (ref "J12") (pin "3") (pinfunction "3_3") (pintype "passive"))
      (node (ref "J13") (pin "3") (pinfunction "3_3") (pintype "passive"))
      (node (ref "J14") (pin "2") (pinfunction "2_2") (pintype "passive"))
      (node (ref "J15") (pin "2") (pinfunction "2_2") (pintype "passive"))
      (node (ref "J16") (pin "2") (pinfunction "2_2") (pintype "passive"))
      (node (ref "J17") (pin "2") (pinfunction "2_2") (pintype "passive"))
      (node (ref "J18") (pin "3") (pinfunction "3_3") (pintype "passive"))
      (node (ref "J19") (pin "2") (pinfunction "G_2") (pintype "passive"))
      (node (ref "J19") (pin "3") (pinfunction "G_3") (pintype "passive"))
      (node (ref "J19") (pin "4") (pinfunction "G_4") (pintype "passive"))
      (node (ref "J19") (pin "5") (pinfunction "G_5") (pintype "passive"))
      (node (ref "J2") (pin "2") (pinfunction "2_2") (pintype "passive"))
      (node (ref "J3") (pin "3") (pinfunction "3_3") (pintype "passive"))
      (node (ref "J4") (pin "2") (pinfunction "2_2") (pintype "passive"))
      (node (ref "J4") (pin "4") (pinfunction "4_4") (pintype "passive"))
      (node (ref "J4") (pin "6") (pinfunction "6_6") (pintype "passive"))
      (node (ref "J5") (pin "2") (pinfunction "G_2") (pintype "passive"))
      (node (ref "J5") (pin "3") (pinfunction "G_3") (pintype "passive"))
      (node (ref "J5") (pin "4") (pinfunction "G_4") (pintype "passive"))
      (node (ref "J5") (pin "5") (pinfunction "G_5") (pintype "passive"))
      (node (ref "J6") (pin "3") (pinfunction "3_3") (pintype "passive"))
      (node (ref "J7") (pin "3") (pinfunction "3_3") (pintype "passive"))
      (node (ref "J8") (pin "3") (pinfunction "3_3") (pintype "passive"))
      (node (ref "J8") (pin "6") (pinfunction "6_6") (pintype "passive"))
      (node (ref "J9") (pin "3") (pinfunction "3_3") (pintype "passive"))
      (node (ref "LED1") (pin "2") (pinfunction "K_2") (pintype "passive"))
      (node (ref "LED2") (pin "2") (pinfunction "K_2") (pintype "passive"))
      (node (ref "LED3") (pin "2") (pinfunction "K_2") (pintype "passive"))
      (node (ref "LED4") (pin "2") (pinfunction "K_2") (pintype "passive"))
      (node (ref "LED5") (pin "2") (pinfunction "K_2") (pintype "passive"))
      (node (ref "LED6") (pin "2") (pinfunction "K_2") (pintype "passive"))
      (node (ref "Q2") (pin "2") (pinfunction "E_2") (pintype "passive"))
      (node (ref "Q3") (pin "2") (pinfunction "E_2") (pintype "passive"))
      (node (ref "R1") (pin "2") (pinfunction "2_2") (pintype "passive"))
      (node (ref "R16") (pin "2") (pinfunction "2_2") (pintype "passive"))
      (node (ref "R17") (pin "2") (pinfunction "2_2") (pintype "passive"))
      (node (ref "R18") (pin "2") (pinfunction "2_2") (pintype "passive"))
      (node (ref "R22") (pin "1") (pinfunction "1_1") (pintype "passive"))
      (node (ref "R23") (pin "2") (pinfunction "2_2") (pintype "passive"))
      (node (ref "R24") (pin "1") (pinfunction "1_1") (pintype "passive"))
      (node (ref "R29") (pin "2") (pinfunction "2_2") (pintype "passive"))
      (node (ref "R3") (pin "2") (pinfunction "2_2") (pintype "passive"))
      (node (ref "R4") (pin "2") (pinfunction "2_2") (pintype "passive"))
      (node (ref "Y1") (pin "2") (pinfunction "NC_2") (pintype "passive"))
      (node (ref "Y1") (pin "3") (pinfunction "NC_3") (pintype "passive"))
      (node (ref "Y2") (pin "2") (pinfunction "GND_2") (pintype "passive"))
      (node (ref "Y2") (pin "4") (pinfunction "GND_4") (pintype "passive"))
    )
    (net (code "45") (name "Net-(BTN1-Pad1)") (class "Default")
      (node (ref "BTN1") (pin "1") (pinfunction "1_1") (pintype "passive"))
      (node (ref "J20") (pin "2") (pinfunction "2_2") (pintype "passive"))
    )
    (net (code "46") (name "Net-(C11-Pad2)") (class "Default")
      (node (ref "C11") (pin "2") (pinfunction "2_2") (pintype "passive"))
      (node (ref "R3") (pin "1") (pinfunction "1_1") (pintype "passive"))
    )
    (net (code "47") (name "Net-(C20-Pad1)") (class "Default")
      (node (ref "C20") (pin "1") (pinfunction "1_1") (pintype "passive"))
      (node (ref "L2") (pin "1") (pinfunction "1_1") (pintype "passive"))
      (node (ref "R21") (pin "1") (pinfunction "1_1") (pintype "passive"))
    )
    (net (code "48") (name "Net-(D1-K)") (class "Default")
      (node (ref "C6") (pin "2") (pinfunction "2_2") (pintype "passive"))
      (node (ref "D1") (pin "1") (pinfunction "K_1") (pintype "passive"))
      (node (ref "IC2") (pin "1") (pinfunction "SW_1") (pintype "passive"))
      (node (ref "L1") (pin "1") (pinfunction "1_1") (pintype "passive"))
    )
    (net (code "49") (name "Net-(IC2-BST)") (class "Default")
      (node (ref "C6") (pin "1") (pinfunction "1_1") (pintype "passive"))
      (node (ref "IC2") (pin "8") (pinfunction "BST_8") (pintype "passive"))
    )
    (net (code "50") (name "Net-(IC2-COMP)") (class "Default")
      (node (ref "C11") (pin "1") (pinfunction "1_1") (pintype "passive"))
      (node (ref "IC2") (pin "3") (pinfunction "COMP_3") (pintype "passive"))
    )
    (net (code "51") (name "Net-(IC2-FB)") (class "Default")
      (node (ref "IC2") (pin "4") (pinfunction "FB_4") (pintype "passive"))
      (node (ref "R2") (pin "2") (pinfunction "2_2") (pintype "passive"))
      (node (ref "R4") (pin "1") (pinfunction "1_1") (pintype "passive"))
    )
    (net (code "52") (name "Net-(IC2-FREQ)") (class "Default")
      (node (ref "IC2") (pin "6") (pinfunction "FREQ_6") (pintype "passive"))
      (node (ref "R1") (pin "1") (pinfunction "1_1") (pintype "passive"))
    )
    (net (code "53") (name "Net-(IC3-BOOT0)") (class "Default")
      (node (ref "IC3") (pin "44") (pinfunction "BOOT0_44") (pintype "passive"))
      (node (ref "R17") (pin "1") (pinfunction "1_1") (pintype "passive"))
    )
    (net (code "54") (name "Net-(IC3-VCAP1)") (class "Default")
      (node (ref "C21") (pin "2") (pinfunction "2_2") (pintype "passive"))
      (node (ref "IC3") (pin "22") (pinfunction "VCAP1_22") (pintype "passive"))
    )
    (net (code "55") (name "Net-(IC4-AD0)") (class "Default")
      (node (ref "IC4") (pin "9") (pinfunction "AD0_9") (pintype "passive"))
      (node (ref "R22") (pin "2") (pinfunction "2_2") (pintype "passive"))
    )
    (net (code "56") (name "Net-(IC4-CPOUT)") (class "Default")
      (node (ref "C19") (pin "1") (pinfunction "1_1") (pintype "passive"))
      (node (ref "IC4") (pin "20") (pinfunction "CPOUT_20") (pintype "passive"))
    )
    (net (code "57") (name "Net-(IC4-REGOUT)") (class "Default")
      (node (ref "C17") (pin "1") (pinfunction "1_1") (pintype "passive"))
      (node (ref "IC4") (pin "10") (pinfunction "REGOUT_10") (pintype "passive"))
    )
    (net (code "58") (name "Net-(IC5-DSEL)") (class "Default")
      (node (ref "IC5") (pin "2") (pinfunction "DSEL_2") (pintype "passive"))
      (node (ref "R23") (pin "1") (pinfunction "1_1") (pintype "passive"))
    )
    (net (code "59") (name "Net-(IC5-NRESET)") (class "Default")
      (node (ref "IC5") (pin "8") (pinfunction "NRESET_8") (pintype "passive"))
      (node (ref "R19") (pin "1") (pinfunction "1_1") (pintype "passive"))
    )
    (net (code "60") (name "Net-(IC5-PULSE)") (class "Default")
      (node (ref "IC5") (pin "3") (pinfunction "PULSE_3") (pintype "passive"))
      (node (ref "R20") (pin "1") (pinfunction "1_1") (pintype "passive"))
    )
    (net (code "61") (name "Net-(IC5-VCCRF)") (class "Default")
      (node (ref "IC5") (pin "9") (pinfunction "VCCRF_9") (pintype "passive"))
      (node (ref "R21") (pin "2") (pinfunction "2_2") (pintype "passive"))
    )
    (net (code "62") (name "Net-(IC9-ANT)") (class "Default")
      (node (ref "IC9") (pin "13") (pinfunction "ANT_13") (pintype "passive"))
      (node (ref "J19") (pin "1") (pinfunction "ANT_1") (pintype "passive"))
    )
    (net (code "63") (name "Net-(IC11-~{MR})") (class "Default")
      (node (ref "IC11") (pin "3") (pinfunction "~{MR}_3") (pintype "passive"))
      (node (ref "J20") (pin "1") (pinfunction "1_1") (pintype "passive"))
    )
    (net (code "64") (name "Net-(J1-Pad1)") (class "Default")
      (node (ref "J1") (pin "1") (pinfunction "1_1") (pintype "passive"))
      (node (ref "Q1") (pin "7") (pinfunction "D1_7") (pintype "passive"))
      (node (ref "Q1") (pin "8") (pinfunction "D1_8") (pintype "passive"))
    )
    (net (code "65") (name "Net-(J2-Pad1)") (class "Default")
      (node (ref "J2") (pin "1") (pinfunction "1_1") (pintype "passive"))
      (node (ref "Q1") (pin "5") (pinfunction "D2_5") (pintype "passive"))
      (node (ref "Q1") (pin "6") (pinfunction "D2_6") (pintype "passive"))
    )
    (net (code "66") (name "Net-(LED1-A)") (class "Default")
      (node (ref "LED1") (pin "1") (pinfunction "A_1") (pintype "passive"))
      (node (ref "R5") (pin "2") (pinfunction "2_2") (pintype "passive"))
    )
    (net (code "67") (name "Net-(LED2-A)") (class "Default")
      (node (ref "LED2") (pin "1") (pinfunction "A_1") (pintype "passive"))
      (node (ref "R6") (pin "2") (pinfunction "2_2") (pintype "passive"))
    )
    (net (code "68") (name "Net-(LED3-A)") (class "Default")
      (node (ref "LED3") (pin "1") (pinfunction "A_1") (pintype "passive"))
      (node (ref "R7") (pin "2") (pinfunction "2_2") (pintype "passive"))
    )
    (net (code "69") (name "Net-(LED4-A)") (class "Default")
      (node (ref "LED4") (pin "1") (pinfunction "A_1") (pintype "passive"))
      (node (ref "R8") (pin "2") (pinfunction "2_2") (pintype "passive"))
    )
    (net (code "70") (name "Net-(LED5-A)") (class "Default")
      (node (ref "LED5") (pin "1") (pinfunction "A_1") (pintype "passive"))
      (node (ref "R9") (pin "2") (pinfunction "2_2") (pintype "passive"))
    )
    (net (code "71") (name "Net-(LED6-A)") (class "Default")
      (node (ref "LED6") (pin "1") (pinfunction "A_1") (pintype "passive"))
      (node (ref "R20") (pin "2") (pinfunction "2_2") (pintype "passive"))
    )
    (net (code "72") (name "Net-(Q1-G1)") (class "Default")
      (node (ref "Q1") (pin "2") (pinfunction "G1_2") (pintype "passive"))
      (node (ref "R11") (pin "2") (pinfunction "2_2") (pintype "passive"))
    )
    (net (code "73") (name "Net-(Q1-G2)") (class "Default")
      (node (ref "Q1") (pin "4") (pinfunction "G2_4") (pintype "passive"))
      (node (ref "R13") (pin "2") (pinfunction "2_2") (pintype "passive"))
    )
    (net (code "74") (name "Net-(Q2-B)") (class "Default")
      (node (ref "Q2") (pin "1") (pinfunction "B_1") (pintype "passive"))
      (node (ref "R14") (pin "2") (pinfunction "2_2") (pintype "passive"))
      (node (ref "R16") (pin "1") (pinfunction "1_1") (pintype "passive"))
    )
    (net (code "75") (name "Net-(Q2-C)") (class "Default")
      (node (ref "Q2") (pin "3") (pinfunction "C_3") (pintype "passive"))
      (node (ref "R10") (pin "2") (pinfunction "2_2") (pintype "passive"))
      (node (ref "R11") (pin "1") (pinfunction "1_1") (pintype "passive"))
    )
    (net (code "76") (name "Net-(Q3-B)") (class "Default")
      (node (ref "Q3") (pin "1") (pinfunction "B_1") (pintype "passive"))
      (node (ref "R15") (pin "2") (pinfunction "2_2") (pintype "passive"))
      (node (ref "R18") (pin "1") (pinfunction "1_1") (pintype "passive"))
    )
    (net (code "77") (name "Net-(Q3-C)") (class "Default")
      (node (ref "Q3") (pin "3") (pinfunction "C_3") (pintype "passive"))
      (node (ref "R12") (pin "2") (pinfunction "2_2") (pintype "passive"))
      (node (ref "R13") (pin "1") (pinfunction "1_1") (pintype "passive"))
    )
    (net (code "78") (name "Net-(Q4-G)") (class "Default")
      (node (ref "Q4") (pin "1") (pinfunction "G_1") (pintype "passive"))
      (node (ref "R29") (pin "1") (pinfunction "1_1") (pintype "passive"))
      (node (ref "Z1") (pin "2") (pinfunction "A_2") (pintype "passive"))
    )
    (net (code "79") (name "Net-(Y1-OSC1)") (class "Default")
      (node (ref "C28") (pin "2") (pinfunction "2_2") (pintype "passive"))
      (node (ref "R28") (pin "1") (pinfunction "1_1") (pintype "passive"))
      (node (ref "Y1") (pin "1") (pinfunction "OSC1_1") (pintype "passive"))
    )
    (net (code "80") (name "Net-(Y2-OSC2)") (class "Default")
      (node (ref "C27") (pin "2") (pinfunction "2_2") (pintype "passive"))
      (node (ref "R27") (pin "1") (pinfunction "1_1") (pintype "passive"))
      (node (ref "Y2") (pin "3") (pinfunction "OSC2_3") (pintype "passive"))
    )
    (net (code "81") (name "SH+") (class "Default")
      (node (ref "IC7") (pin "10") (pinfunction "IN+_10") (pintype "passive"))
      (node (ref "IC7") (pin "8") (pinfunction "VBUS_8") (pintype "passive"))
      (node (ref "J18") (pin "2") (pinfunction "2_2") (pintype "passive"))
      (node (ref "Q4") (pin "2") (pinfunction "D_2") (pintype "passive"))
    )
    (net (code "82") (name "SH-") (class "Default")
      (node (ref "IC7") (pin "9") (pinfunction "IN-_9") (pintype "passive"))
      (node (ref "J18") (pin "1") (pinfunction "1_1") (pintype "passive"))
    )
    (net (code "83") (name "unconnected-(IC2-EN-Pad2)") (class "Default")
      (node (ref "IC2") (pin "2") (pinfunction "EN_2") (pintype "passive+no_connect"))
    )
    (net (code "84") (name "unconnected-(IC3-PA4-Pad14)") (class "Default")
      (node (ref "IC3") (pin "14") (pinfunction "PA4_14") (pintype "passive"))
    )
    (net (code "85") (name "unconnected-(IC4-AUXCL-Pad7)") (class "Default")
      (node (ref "IC4") (pin "7") (pinfunction "AUXCL_7") (pintype "passive+no_connect"))
    )
    (net (code "86") (name "unconnected-(IC4-AUXDA-Pad6)") (class "Default")
      (node (ref "IC4") (pin "6") (pinfunction "AUXDA_6") (pintype "passive+no_connect"))
    )
    (net (code "87") (name "unconnected-(IC4-INT-Pad12)") (class "Default")
      (node (ref "IC4") (pin "12") (pinfunction "INT_12") (pintype "passive+no_connect"))
    )
    (net (code "88") (name "unconnected-(IC4-NC-Pad2)") (class "Default")
      (node (ref "IC4") (pin "2") (pinfunction "NC_2") (pintype "passive+no_connect"))
    )
    (net (code "89") (name "unconnected-(IC4-NC-Pad3)") (class "Default")
      (node (ref "IC4") (pin "3") (pinfunction "NC_3") (pintype "passive+no_connect"))
    )
    (net (code "90") (name "unconnected-(IC4-NC-Pad4)") (class "Default")
      (node (ref "IC4") (pin "4") (pinfunction "NC_4") (pintype "passive+no_connect"))
    )
    (net (code "91") (name "unconnected-(IC4-NC-Pad5)") (class "Default")
      (node (ref "IC4") (pin "5") (pinfunction "NC_5") (pintype "passive+no_connect"))
    )
    (net (code "92") (name "unconnected-(IC4-NC-Pad14)") (class "Default")
      (node (ref "IC4") (pin "14") (pinfunction "NC_14") (pintype "passive+no_connect"))
    )
    (net (code "93") (name "unconnected-(IC4-NC-Pad15)") (class "Default")
      (node (ref "IC4") (pin "15") (pinfunction "NC_15") (pintype "passive+no_connect"))
    )
    (net (code "94") (name "unconnected-(IC4-NC-Pad16)") (class "Default")
      (node (ref "IC4") (pin "16") (pinfunction "NC_16") (pintype "passive+no_connect"))
    )
    (net (code "95") (name "unconnected-(IC4-NC-Pad17)") (class "Default")
      (node (ref "IC4") (pin "17") (pinfunction "NC_17") (pintype "passive+no_connect"))
    )
    (net (code "96") (name "unconnected-(IC4-RESV1-Pad19)") (class "Default")
      (node (ref "IC4") (pin "19") (pinfunction "RESV1_19") (pintype "passive+no_connect"))
    )
    (net (code "97") (name "unconnected-(IC4-RESV2-Pad21)") (class "Default")
      (node (ref "IC4") (pin "21") (pinfunction "RESV2_21") (pintype "passive+no_connect"))
    )
    (net (code "98") (name "unconnected-(IC4-RESV3-Pad22)") (class "Default")
      (node (ref "IC4") (pin "22") (pinfunction "RESV3_22") (pintype "passive+no_connect"))
    )
    (net (code "99") (name "unconnected-(IC5-ANTON-Pad14)") (class "Default")
      (node (ref "IC5") (pin "14") (pinfunction "ANTON_14") (pintype "passive+no_connect"))
    )
    (net (code "100") (name "unconnected-(IC5-EXINT0-Pad4)") (class "Default")
      (node (ref "IC5") (pin "4") (pinfunction "EXINT0_4") (pintype "passive+no_connect"))
    )
    (net (code "101") (name "unconnected-(IC5-EXINT1-Pad15)") (class "Default")
      (node (ref "IC5") (pin "15") (pinfunction "EXINT1_15") (pintype "passive+no_connect"))
    )
    (net (code "102") (name "unconnected-(IC5-RES-Pad16)") (class "Default")
      (node (ref "IC5") (pin "16") (pinfunction "RES_16") (pintype "passive+no_connect"))
    )
    (net (code "103") (name "unconnected-(IC5-RES-Pad17)") (class "Default")
      (node (ref "IC5") (pin "17") (pinfunction "RES_17") (pintype "passive+no_connect"))
    )
    (net (code "104") (name "unconnected-(IC5-SAFEB-Pad1)") (class "Default")
      (node (ref "IC5") (pin "1") (pinfunction "SAFEB_1") (pintype "passive+no_connect"))
    )
    (net (code "105") (name "unconnected-(IC5-USBDM-Pad5)") (class "Default")
      (node (ref "IC5") (pin "5") (pinfunction "USBDM_5") (pintype "passive+no_connect"))
    )
    (net (code "106") (name "unconnected-(IC5-USBDP-Pad6)") (class "Default")
      (node (ref "IC5") (pin "6") (pinfunction "USBDP_6") (pintype "passive+no_connect"))
    )
    (net (code "107") (name "unconnected-(IC5-VDDUSB-Pad7)") (class "Default")
      (node (ref "IC5") (pin "7") (pinfunction "VDDUSB_7") (pintype "passive+no_connect"))
    )
    (net (code "108") (name "unconnected-(IC9-DIO1-Pad2)") (class "Default")
      (node (ref "IC9") (pin "2") (pinfunction "DIO1_2") (pintype "passive+no_connect"))
    )
    (net (code "109") (name "unconnected-(IC9-DIO2-Pad3)") (class "Default")
      (node (ref "IC9") (pin "3") (pinfunction "DIO2_3") (pintype "passive+no_connect"))
    )
    (net (code "110") (name "unconnected-(IC9-DIO3-Pad4)") (class "Default")
      (node (ref "IC9") (pin "4") (pinfunction "DIO3_4") (pintype "passive+no_connect"))
    )
    (net (code "111") (name "unconnected-(IC10-3V-Pad6)") (class "Default")
      (node (ref "IC10") (pin "6") (pinfunction "3V_6") (pintype "power_in+no_connect"))
    )
    (net (code "112") (name "unconnected-(IC10-ADR-Pad2)") (class "Default")
      (node (ref "IC10") (pin "2") (pinfunction "ADR_2") (pintype "power_in+no_connect"))
    )
    (net (code "113") (name "unconnected-(IC10-INT-Pad1)") (class "Default")
      (node (ref "IC10") (pin "1") (pinfunction "INT_1") (pintype "power_in+no_connect"))
    )
    (net (code "114") (name "unconnected-(IC10-PS0-Pad3)") (class "Default")
      (node (ref "IC10") (pin "3") (pinfunction "PS0_3") (pintype "power_in+no_connect"))
    )
    (net (code "115") (name "unconnected-(IC10-PS1-Pad4)") (class "Default")
      (node (ref "IC10") (pin "4") (pinfunction "PS1_4") (pintype "power_in+no_connect"))
    )
    (net (code "116") (name "unconnected-(J3-Pad2)") (class "Default")
      (node (ref "J3") (pin "2") (pinfunction "2_2") (pintype "passive+no_connect"))
    )
    (net (code "117") (name "unconnected-(J6-Pad2)") (class "Default")
      (node (ref "J6") (pin "2") (pinfunction "2_2") (pintype "passive+no_connect"))
    )
    (net (code "118") (name "unconnected-(J9-Pad2)") (class "Default")
      (node (ref "J9") (pin "2") (pinfunction "2_2") (pintype "passive+no_connect"))
    )
    (net (code "119") (name "unconnected-(J12-Pad2)") (class "Default")
      (node (ref "J12") (pin "2") (pinfunction "2_2") (pintype "passive+no_connect"))
    )
  )
)
